# NacelleV2.net
KiCad netlist of a schematic drawn in Altium Designer
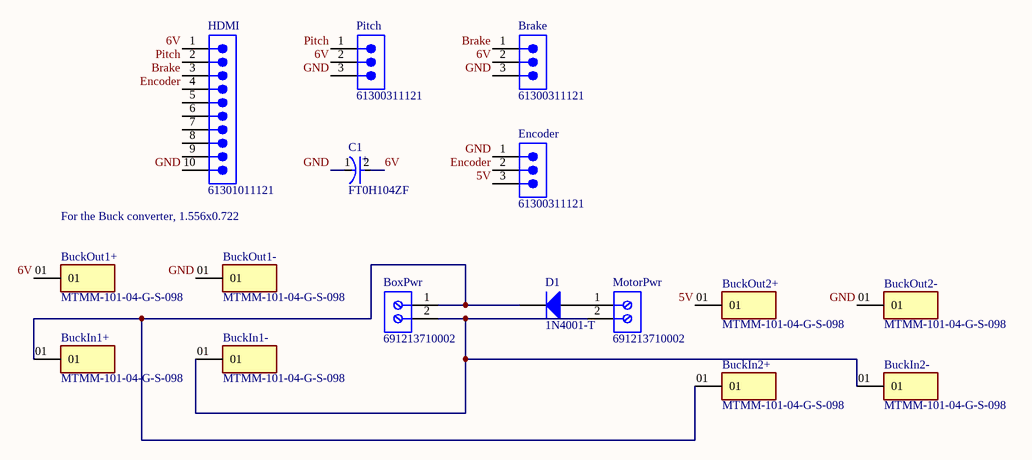
[diagram p0: NacelleV2.SchDoc]

(export (version "E")
  (design (tool "Eeschema 10.0.6"))
  (components
    (comp (ref "BoxPwr")
      (value "691213710002")
      (footprint "691213710002")
      (fields (field (name "VOLTAGE") "300V"))
      (libsource (lib "Altium Content Vault") (part "TBL - 1R - 02P - Screw"))
    )
    (comp (ref "Brake")
      (value "61300311121")
      (footprint "61300311121")
      (libsource (lib "Altium Content Vault") (part "Header_Male_1R_03P"))
    )
    (comp (ref "BuckIn1+")
      (value "MTMM-101-04-G-S-098")
      (footprint "SAMTEC_MTMM-101-04-G-S-098")
      (description "Connector Header Through Hole 1 position -")
      (fields (field (name "MF") "Samtec"))
      (libsource (lib "MTMM-101-04-G-S-098") (part "MTMM-101-04-G-S-098"))
    )
    (comp (ref "BuckIn1-")
      (value "MTMM-101-04-G-S-098")
      (footprint "SAMTEC_MTMM-101-04-G-S-098")
      (description "Connector Header Through Hole 1 position -")
      (fields (field (name "MF") "Samtec"))
      (libsource (lib "MTMM-101-04-G-S-098") (part "MTMM-101-04-G-S-098"))
    )
    (comp (ref "BuckIn2+")
      (value "MTMM-101-04-G-S-098")
      (footprint "SAMTEC_MTMM-101-04-G-S-098")
      (description "Connector Header Through Hole 1 position -")
      (fields (field (name "MF") "Samtec"))
      (libsource (lib "MTMM-101-04-G-S-098") (part "MTMM-101-04-G-S-098"))
    )
    (comp (ref "BuckIn2-")
      (value "MTMM-101-04-G-S-098")
      (footprint "SAMTEC_MTMM-101-04-G-S-098")
      (description "Connector Header Through Hole 1 position -")
      (fields (field (name "MF") "Samtec"))
      (libsource (lib "MTMM-101-04-G-S-098") (part "MTMM-101-04-G-S-098"))
    )
    (comp (ref "BuckOut1+")
      (value "MTMM-101-04-G-S-098")
      (footprint "SAMTEC_MTMM-101-04-G-S-098")
      (description "Connector Header Through Hole 1 position -")
      (fields (field (name "MF") "Samtec"))
      (libsource (lib "MTMM-101-04-G-S-098") (part "MTMM-101-04-G-S-098"))
    )
    (comp (ref "BuckOut1-")
      (value "MTMM-101-04-G-S-098")
      (footprint "SAMTEC_MTMM-101-04-G-S-098")
      (description "Connector Header Through Hole 1 position -")
      (fields (field (name "MF") "Samtec"))
      (libsource (lib "MTMM-101-04-G-S-098") (part "MTMM-101-04-G-S-098"))
    )
    (comp (ref "BuckOut2+")
      (value "MTMM-101-04-G-S-098")
      (footprint "SAMTEC_MTMM-101-04-G-S-098")
      (description "Connector Header Through Hole 1 position -")
      (fields (field (name "MF") "Samtec"))
      (libsource (lib "MTMM-101-04-G-S-098") (part "MTMM-101-04-G-S-098"))
    )
    (comp (ref "BuckOut2-")
      (value "MTMM-101-04-G-S-098")
      (footprint "SAMTEC_MTMM-101-04-G-S-098")
      (description "Connector Header Through Hole 1 position -")
      (fields (field (name "MF") "Samtec"))
      (libsource (lib "MTMM-101-04-G-S-098") (part "MTMM-101-04-G-S-098"))
    )
    (comp (ref "C1")
      (value "FT0H104ZF")
      (footprint "FP-FT0H104ZF-MFG")
      (description "CAP 100MF -20% +80% 5.5V T/H")
      (fields
        (field (name "OCTOPART") "https://octopart.com/ft0h104zf-kemet-30531663")
        (field (name "MANUFACTURER") "KEMET")
      )
      (libsource (lib "Altium Content Vault") (part "cf48714ba7e38822c1575c7ec0b6d1f"))
    )
    (comp (ref "D1")
      (value "1N4001-T")
      (footprint "DIOD-DO-41-P-2_V")
      (description "1.0 A Rectifier, 15 pF, 50 V, -65 to 150 degC, 2-Pin DO-41 Plastic, RoHS, Tape and Reel")
      (fields (field (name "MANUFACTURER") "Diodes Inc"))
      (libsource (lib "Altium Content Vault") (part "DIOD-D-A1K2-2"))
    )
    (comp (ref "Encoder")
      (value "61300311121")
      (footprint "61300311121")
      (libsource (lib "Altium Content Vault") (part "Header_Male_1R_03P"))
    )
    (comp (ref "HDMI")
      (value "61301011121")
      (footprint "61301011121")
      (libsource (lib "Altium Content Vault") (part "Header_Male_1R_10P"))
    )
    (comp (ref "MotorPwr")
      (value "691213710002")
      (footprint "691213710002")
      (fields (field (name "VOLTAGE") "300V"))
      (libsource (lib "Altium Content Vault") (part "TBL - 1R - 02P - Screw"))
    )
    (comp (ref "Pitch")
      (value "61300311121")
      (footprint "61300311121")
      (libsource (lib "Altium Content Vault") (part "Header_Male_1R_03P"))
    )
  )
  (nets
    (net (code "1") (name "/5V") (class "Default")
      (node (ref "BuckOut2+") (pin "01") (pinfunction "01_01") (pintype "passive"))
      (node (ref "Encoder") (pin "3") (pinfunction "3_3") (pintype "passive"))
    )
    (net (code "2") (name "/6V") (class "Default")
      (node (ref "Brake") (pin "2") (pinfunction "2_2") (pintype "passive"))
      (node (ref "BuckOut1+") (pin "01") (pinfunction "01_01") (pintype "passive"))
      (node (ref "C1") (pin "2") (pinfunction "A_2") (pintype "passive"))
      (node (ref "HDMI") (pin "1") (pinfunction "1_1") (pintype "passive"))
      (node (ref "Pitch") (pin "2") (pinfunction "2_2") (pintype "passive"))
    )
    (net (code "3") (name "/Brake") (class "Default")
      (node (ref "Brake") (pin "1") (pinfunction "1_1") (pintype "passive"))
      (node (ref "HDMI") (pin "3") (pinfunction "3_3") (pintype "passive"))
    )
    (net (code "4") (name "/Encoder") (class "Default")
      (node (ref "Encoder") (pin "2") (pinfunction "2_2") (pintype "passive"))
      (node (ref "HDMI") (pin "4") (pinfunction "4_4") (pintype "passive"))
    )
    (net (code "5") (name "/GND") (class "Default")
      (node (ref "Brake") (pin "3") (pinfunction "3_3") (pintype "passive"))
      (node (ref "BuckOut1-") (pin "01") (pinfunction "01_01") (pintype "passive"))
      (node (ref "BuckOut2-") (pin "01") (pinfunction "01_01") (pintype "passive"))
      (node (ref "C1") (pin "1") (pinfunction "C_1") (pintype "passive"))
      (node (ref "Encoder") (pin "1") (pinfunction "1_1") (pintype "passive"))
      (node (ref "HDMI") (pin "10") (pinfunction "10_10") (pintype "passive"))
      (node (ref "Pitch") (pin "3") (pinfunction "3_3") (pintype "passive"))
    )
    (net (code "6") (name "/Pitch") (class "Default")
      (node (ref "HDMI") (pin "2") (pinfunction "2_2") (pintype "passive"))
      (node (ref "Pitch") (pin "1") (pinfunction "1_1") (pintype "passive"))
    )
    (net (code "7") (name "Net-(BoxPwr-Pad2)") (class "Default")
      (node (ref "BoxPwr") (pin "2") (pinfunction "2_2") (pintype "passive"))
      (node (ref "BuckIn1-") (pin "01") (pinfunction "01_01") (pintype "passive"))
      (node (ref "BuckIn2-") (pin "01") (pinfunction "01_01") (pintype "passive"))
      (node (ref "MotorPwr") (pin "2") (pinfunction "2_2") (pintype "passive"))
    )
    (net (code "8") (name "Net-(D1-A)") (class "Default")
      (node (ref "D1") (pin "1") (pinfunction "A_1") (pintype "passive"))
      (node (ref "MotorPwr") (pin "1") (pinfunction "1_1") (pintype "passive"))
    )
    (net (code "9") (name "Net-(D1-K)") (class "Default")
      (node (ref "BoxPwr") (pin "1") (pinfunction "1_1") (pintype "passive"))
      (node (ref "BuckIn1+") (pin "01") (pinfunction "01_01") (pintype "passive"))
      (node (ref "BuckIn2+") (pin "01") (pinfunction "01_01") (pintype "passive"))
      (node (ref "D1") (pin "2") (pinfunction "K_2") (pintype "passive"))
    )
    (net (code "10") (name "unconnected-(HDMI-Pad5)") (class "Default")
      (node (ref "HDMI") (pin "5") (pinfunction "5_5") (pintype "passive"))
    )
    (net (code "11") (name "unconnected-(HDMI-Pad6)") (class "Default")
      (node (ref "HDMI") (pin "6") (pinfunction "6_6") (pintype "passive"))
    )
    (net (code "12") (name "unconnected-(HDMI-Pad7)") (class "Default")
      (node (ref "HDMI") (pin "7") (pinfunction "7_7") (pintype "passive"))
    )
    (net (code "13") (name "unconnected-(HDMI-Pad8)") (class "Default")
      (node (ref "HDMI") (pin "8") (pinfunction "8_8") (pintype "passive"))
    )
    (net (code "14") (name "unconnected-(HDMI-Pad9)") (class "Default")
      (node (ref "HDMI") (pin "9") (pinfunction "9_9") (pintype "passive"))
    )
  )
)
